# rapidshark-main-breakout-top-mk-1_3.net
KiCad netlist of a schematic drawn in EAGLE
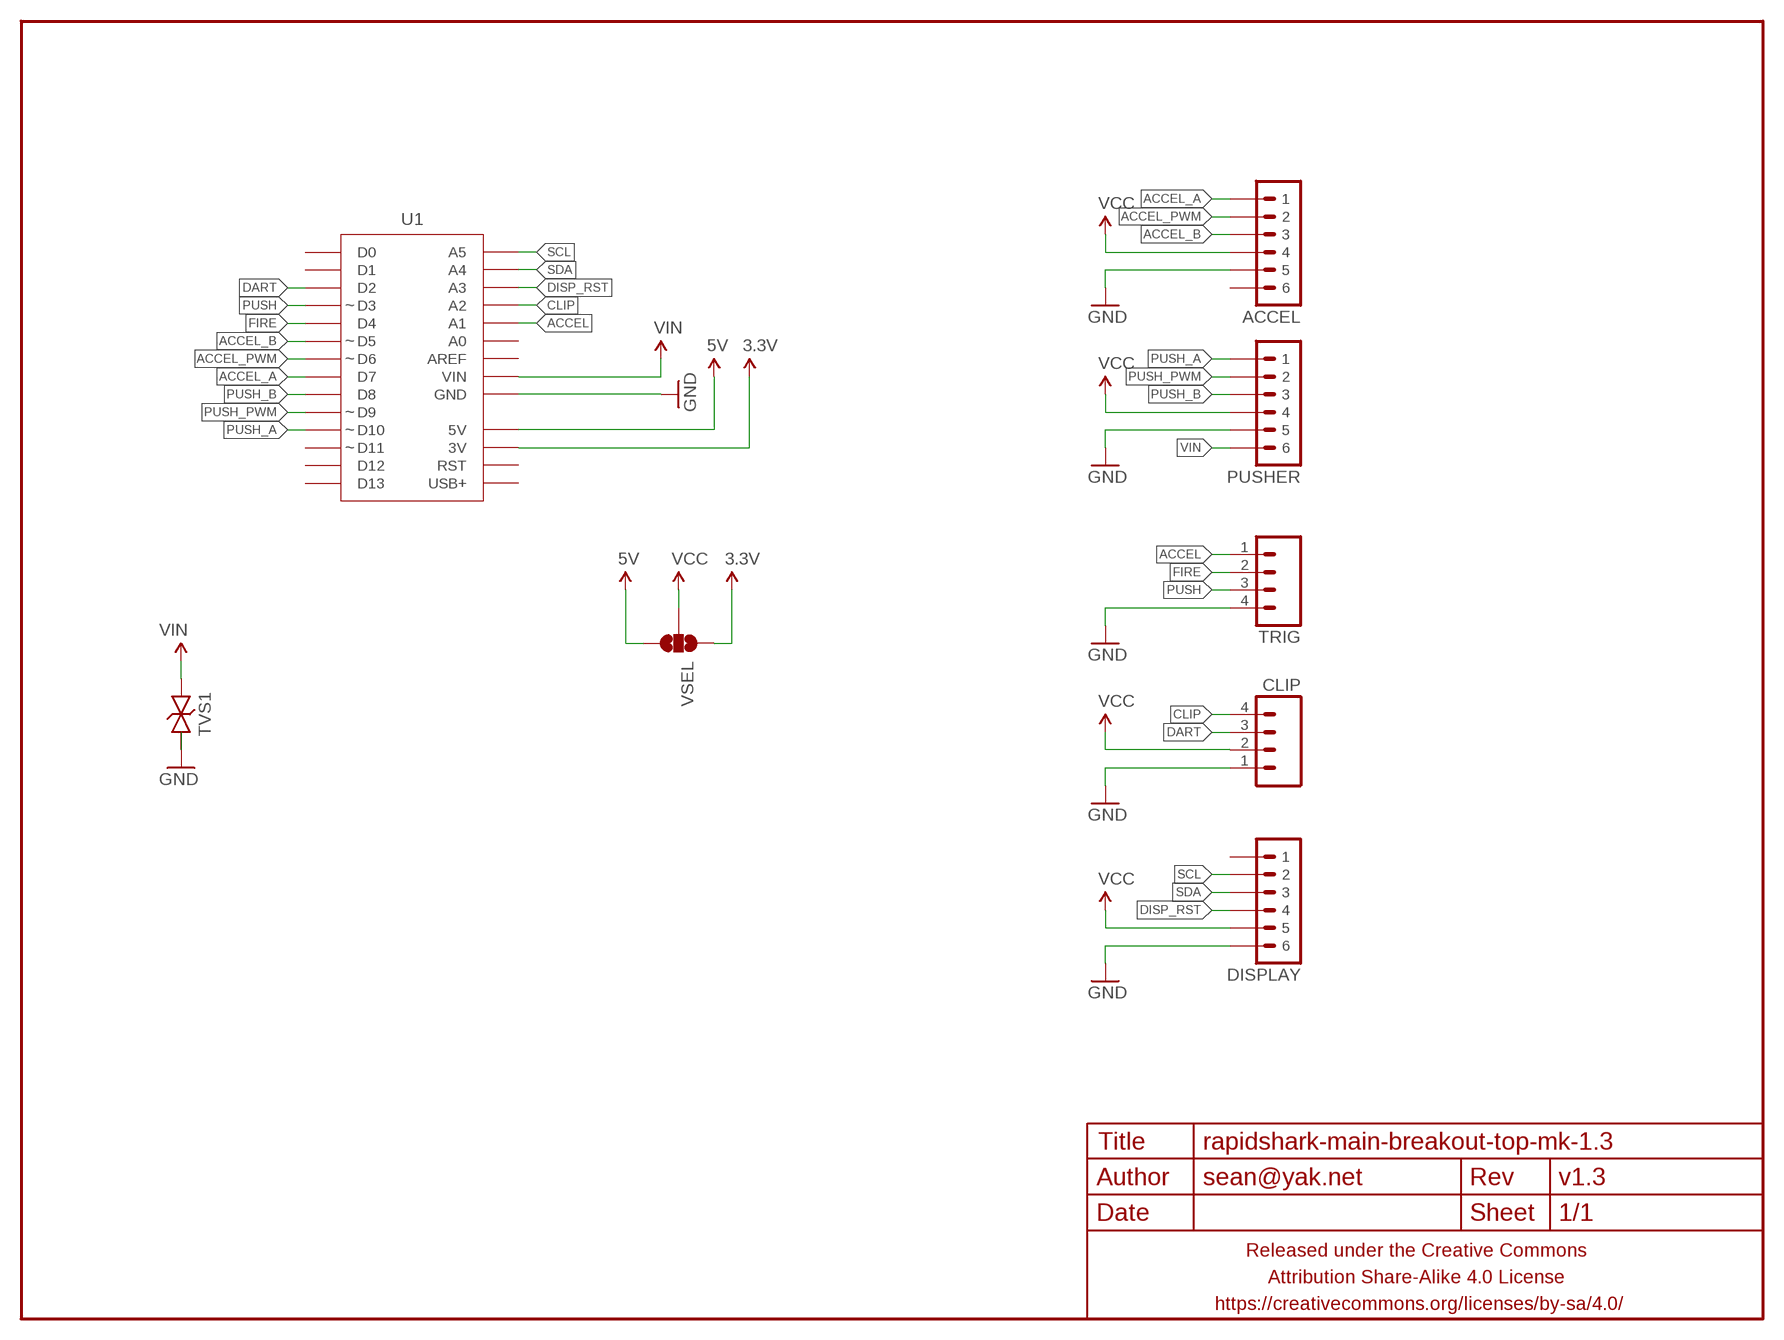
[diagram p0: schematic, sheet 1]

(export (version "E")
  (design (tool "Eeschema 10.0.6"))
  (components
    (comp (ref "ACCEL")
      (value "M06JST-PH-PTH-VERT")
      (footprint "eagle-import:JST-6-PH-VERT-PTH")
      (libsource (lib "eagle-import") (part "M06JST-PH-PTH-VERT"))
    )
    (comp (ref "CLIP")
      (value "M04JST-PTH-VERT")
      (footprint "eagle-import:JST-4-PH-VERT-PTH")
      (libsource (lib "eagle-import") (part "M04JST-PTH-VERT"))
    )
    (comp (ref "DISPLAY")
      (value "M06JST-PH-PTH-VERT")
      (footprint "eagle-import:JST-6-PH-VERT-PTH")
      (libsource (lib "eagle-import") (part "M06JST-PH-PTH-VERT"))
    )
    (comp (ref "FRAME1")
      (value "FRAME-LETTERNO_PACKAGE")
      (footprint "eagle-import:DUMMY")
      (fields (field (name "DESIGNER") "sean@yak.net") (field (name "VERSION") "v1.3"))
      (libsource (lib "eagle-import") (part "FRAME-LETTERNO_PACKAGE"))
    )
    (comp (ref "PUSHER")
      (value "M06JST-PH-PTH-VERT")
      (footprint "eagle-import:JST-6-PH-VERT-PTH")
      (libsource (lib "eagle-import") (part "M06JST-PH-PTH-VERT"))
    )
    (comp (ref "TRIG")
      (value "M04JST-PTH-VERT")
      (footprint "eagle-import:JST-4-PH-VERT-PTH")
      (libsource (lib "eagle-import") (part "M04JST-PTH-VERT"))
    )
    (comp (ref "TVS1")
      (value "TVSDO-41-8.89MM")
      (footprint "eagle-import:DO-41-TVS-BI-8.89MM")
      (libsource (lib "eagle-import") (part "TVSDO-41-8.89MM"))
    )
    (comp (ref "U1")
      (value "ADAFRUIT_METRO_MININOSILK-ABMBI")
      (footprint "eagle-import:ADAFRUIT_METRO_MINI_FLIPPED")
      (libsource (lib "eagle-import") (part "ADAFRUIT_METRO_MININOSILK-ABMBI"))
    )
    (comp (ref "VSEL")
      (value "JUMPER-PAD-3-NOFULL_BOX_SILK")
      (footprint "eagle-import:PAD-JUMPER-3-NO_YES_SILK_FULL_BOX")
      (libsource (lib "eagle-import") (part "JUMPER-PAD-3-NOFULL_BOX_SILK"))
    )
  )
  (nets
    (net (code "1") (name "3.3V") (class "Default")
      (node (ref "U1") (pin "17") (pinfunction "3V_17") (pintype "bidirectional"))
      (node (ref "VSEL") (pin "1") (pinfunction "1_1") (pintype "passive"))
    )
    (net (code "2") (name "5V") (class "Default")
      (node (ref "U1") (pin "18") (pinfunction "5V_18") (pintype "bidirectional"))
      (node (ref "VSEL") (pin "3") (pinfunction "3_3") (pintype "passive"))
    )
    (net (code "3") (name "ACCEL") (class "Default")
      (node (ref "TRIG") (pin "1") (pinfunction "1_1") (pintype "passive"))
      (node (ref "U1") (pin "24") (pinfunction "A1_24") (pintype "bidirectional"))
    )
    (net (code "4") (name "ACCEL_A") (class "Default")
      (node (ref "ACCEL") (pin "1") (pinfunction "1_1") (pintype "passive"))
      (node (ref "U1") (pin "8") (pinfunction "D7_8") (pintype "bidirectional"))
    )
    (net (code "5") (name "ACCEL_B") (class "Default")
      (node (ref "ACCEL") (pin "3") (pinfunction "3_3") (pintype "passive"))
      (node (ref "U1") (pin "6") (pinfunction "D5_6") (pintype "bidirectional"))
    )
    (net (code "6") (name "ACCEL_PWM") (class "Default")
      (node (ref "ACCEL") (pin "2") (pinfunction "2_2") (pintype "passive"))
      (node (ref "U1") (pin "7") (pinfunction "D6_7") (pintype "bidirectional"))
    )
    (net (code "7") (name "CLIP") (class "Default")
      (node (ref "CLIP") (pin "4") (pinfunction "4_4") (pintype "passive"))
      (node (ref "U1") (pin "25") (pinfunction "A2_25") (pintype "bidirectional"))
    )
    (net (code "8") (name "DART") (class "Default")
      (node (ref "CLIP") (pin "3") (pinfunction "3_3") (pintype "passive"))
      (node (ref "U1") (pin "3") (pinfunction "D2_3") (pintype "bidirectional"))
    )
    (net (code "9") (name "DISP_RST") (class "Default")
      (node (ref "DISPLAY") (pin "4") (pinfunction "4_4") (pintype "passive"))
      (node (ref "U1") (pin "26") (pinfunction "A3_26") (pintype "bidirectional"))
    )
    (net (code "10") (name "FIRE") (class "Default")
      (node (ref "TRIG") (pin "2") (pinfunction "2_2") (pintype "passive"))
      (node (ref "U1") (pin "5") (pinfunction "D4_5") (pintype "bidirectional"))
    )
    (net (code "11") (name "GND") (class "Default")
      (node (ref "ACCEL") (pin "5") (pinfunction "5_5") (pintype "passive"))
      (node (ref "CLIP") (pin "1") (pinfunction "1_1") (pintype "passive"))
      (node (ref "DISPLAY") (pin "6") (pinfunction "6_6") (pintype "passive"))
      (node (ref "PUSHER") (pin "5") (pinfunction "5_5") (pintype "passive"))
      (node (ref "TRIG") (pin "4") (pinfunction "4_4") (pintype "passive"))
      (node (ref "TVS1") (pin "P$1") (pinfunction "1_P$1") (pintype "passive"))
      (node (ref "U1") (pin "19") (pinfunction "GND_19") (pintype "bidirectional"))
      (node (ref "U1") (pin "20") (pinfunction "GND_20") (pintype "bidirectional"))
    )
    (net (code "12") (name "PUSH") (class "Default")
      (node (ref "TRIG") (pin "3") (pinfunction "3_3") (pintype "passive"))
      (node (ref "U1") (pin "4") (pinfunction "D3_4") (pintype "bidirectional"))
    )
    (net (code "13") (name "PUSH_A") (class "Default")
      (node (ref "PUSHER") (pin "1") (pinfunction "1_1") (pintype "passive"))
      (node (ref "U1") (pin "11") (pinfunction "D10_11") (pintype "bidirectional"))
    )
    (net (code "14") (name "PUSH_B") (class "Default")
      (node (ref "PUSHER") (pin "3") (pinfunction "3_3") (pintype "passive"))
      (node (ref "U1") (pin "9") (pinfunction "D8_9") (pintype "bidirectional"))
    )
    (net (code "15") (name "PUSH_PWM") (class "Default")
      (node (ref "PUSHER") (pin "2") (pinfunction "2_2") (pintype "passive"))
      (node (ref "U1") (pin "10") (pinfunction "D9_10") (pintype "bidirectional"))
    )
    (net (code "16") (name "SCL") (class "Default")
      (node (ref "DISPLAY") (pin "2") (pinfunction "2_2") (pintype "passive"))
      (node (ref "U1") (pin "28") (pinfunction "A5_28") (pintype "bidirectional"))
    )
    (net (code "17") (name "SDA") (class "Default")
      (node (ref "DISPLAY") (pin "3") (pinfunction "3_3") (pintype "passive"))
      (node (ref "U1") (pin "27") (pinfunction "A4_27") (pintype "bidirectional"))
    )
    (net (code "18") (name "VCC") (class "Default")
      (node (ref "ACCEL") (pin "4") (pinfunction "4_4") (pintype "passive"))
      (node (ref "CLIP") (pin "2") (pinfunction "2_2") (pintype "passive"))
      (node (ref "DISPLAY") (pin "5") (pinfunction "5_5") (pintype "passive"))
      (node (ref "PUSHER") (pin "4") (pinfunction "4_4") (pintype "passive"))
      (node (ref "VSEL") (pin "2") (pinfunction "2_2") (pintype "passive"))
    )
    (net (code "19") (name "VIN") (class "Default")
      (node (ref "PUSHER") (pin "6") (pinfunction "6_6") (pintype "passive"))
      (node (ref "TVS1") (pin "P$2") (pinfunction "2_P$2") (pintype "passive"))
      (node (ref "U1") (pin "21") (pinfunction "VIN_21") (pintype "bidirectional"))
    )
    (net (code "20") (name "unconnected-(ACCEL-Pad6)") (class "Default")
      (node (ref "ACCEL") (pin "6") (pinfunction "6_6") (pintype "passive"))
    )
    (net (code "21") (name "unconnected-(DISPLAY-Pad1)") (class "Default")
      (node (ref "DISPLAY") (pin "1") (pinfunction "1_1") (pintype "passive"))
    )
    (net (code "22") (name "unconnected-(U1-A0-Pad23)") (class "Default")
      (node (ref "U1") (pin "23") (pinfunction "A0_23") (pintype "bidirectional"))
    )
    (net (code "23") (name "unconnected-(U1-AREF-Pad22)") (class "Default")
      (node (ref "U1") (pin "22") (pinfunction "AREF_22") (pintype "bidirectional"))
    )
    (net (code "24") (name "unconnected-(U1-D0-Pad1)") (class "Default")
      (node (ref "U1") (pin "1") (pinfunction "D0_1") (pintype "bidirectional"))
    )
    (net (code "25") (name "unconnected-(U1-D1-Pad2)") (class "Default")
      (node (ref "U1") (pin "2") (pinfunction "D1_2") (pintype "bidirectional"))
    )
    (net (code "26") (name "unconnected-(U1-D11-Pad12)") (class "Default")
      (node (ref "U1") (pin "12") (pinfunction "D11_12") (pintype "bidirectional"))
    )
    (net (code "27") (name "unconnected-(U1-D12-Pad13)") (class "Default")
      (node (ref "U1") (pin "13") (pinfunction "D12_13") (pintype "bidirectional"))
    )
    (net (code "28") (name "unconnected-(U1-D13-Pad14)") (class "Default")
      (node (ref "U1") (pin "14") (pinfunction "D13_14") (pintype "bidirectional"))
    )
    (net (code "29") (name "unconnected-(U1-RST-Pad16)") (class "Default")
      (node (ref "U1") (pin "16") (pinfunction "RST_16") (pintype "bidirectional"))
    )
    (net (code "30") (name "unconnected-(U1-USB+-Pad15)") (class "Default")
      (node (ref "U1") (pin "15") (pinfunction "USB+_15") (pintype "bidirectional"))
    )
  )
)
